# USB.net
KiCad netlist of a schematic drawn in EasyEDA Pro
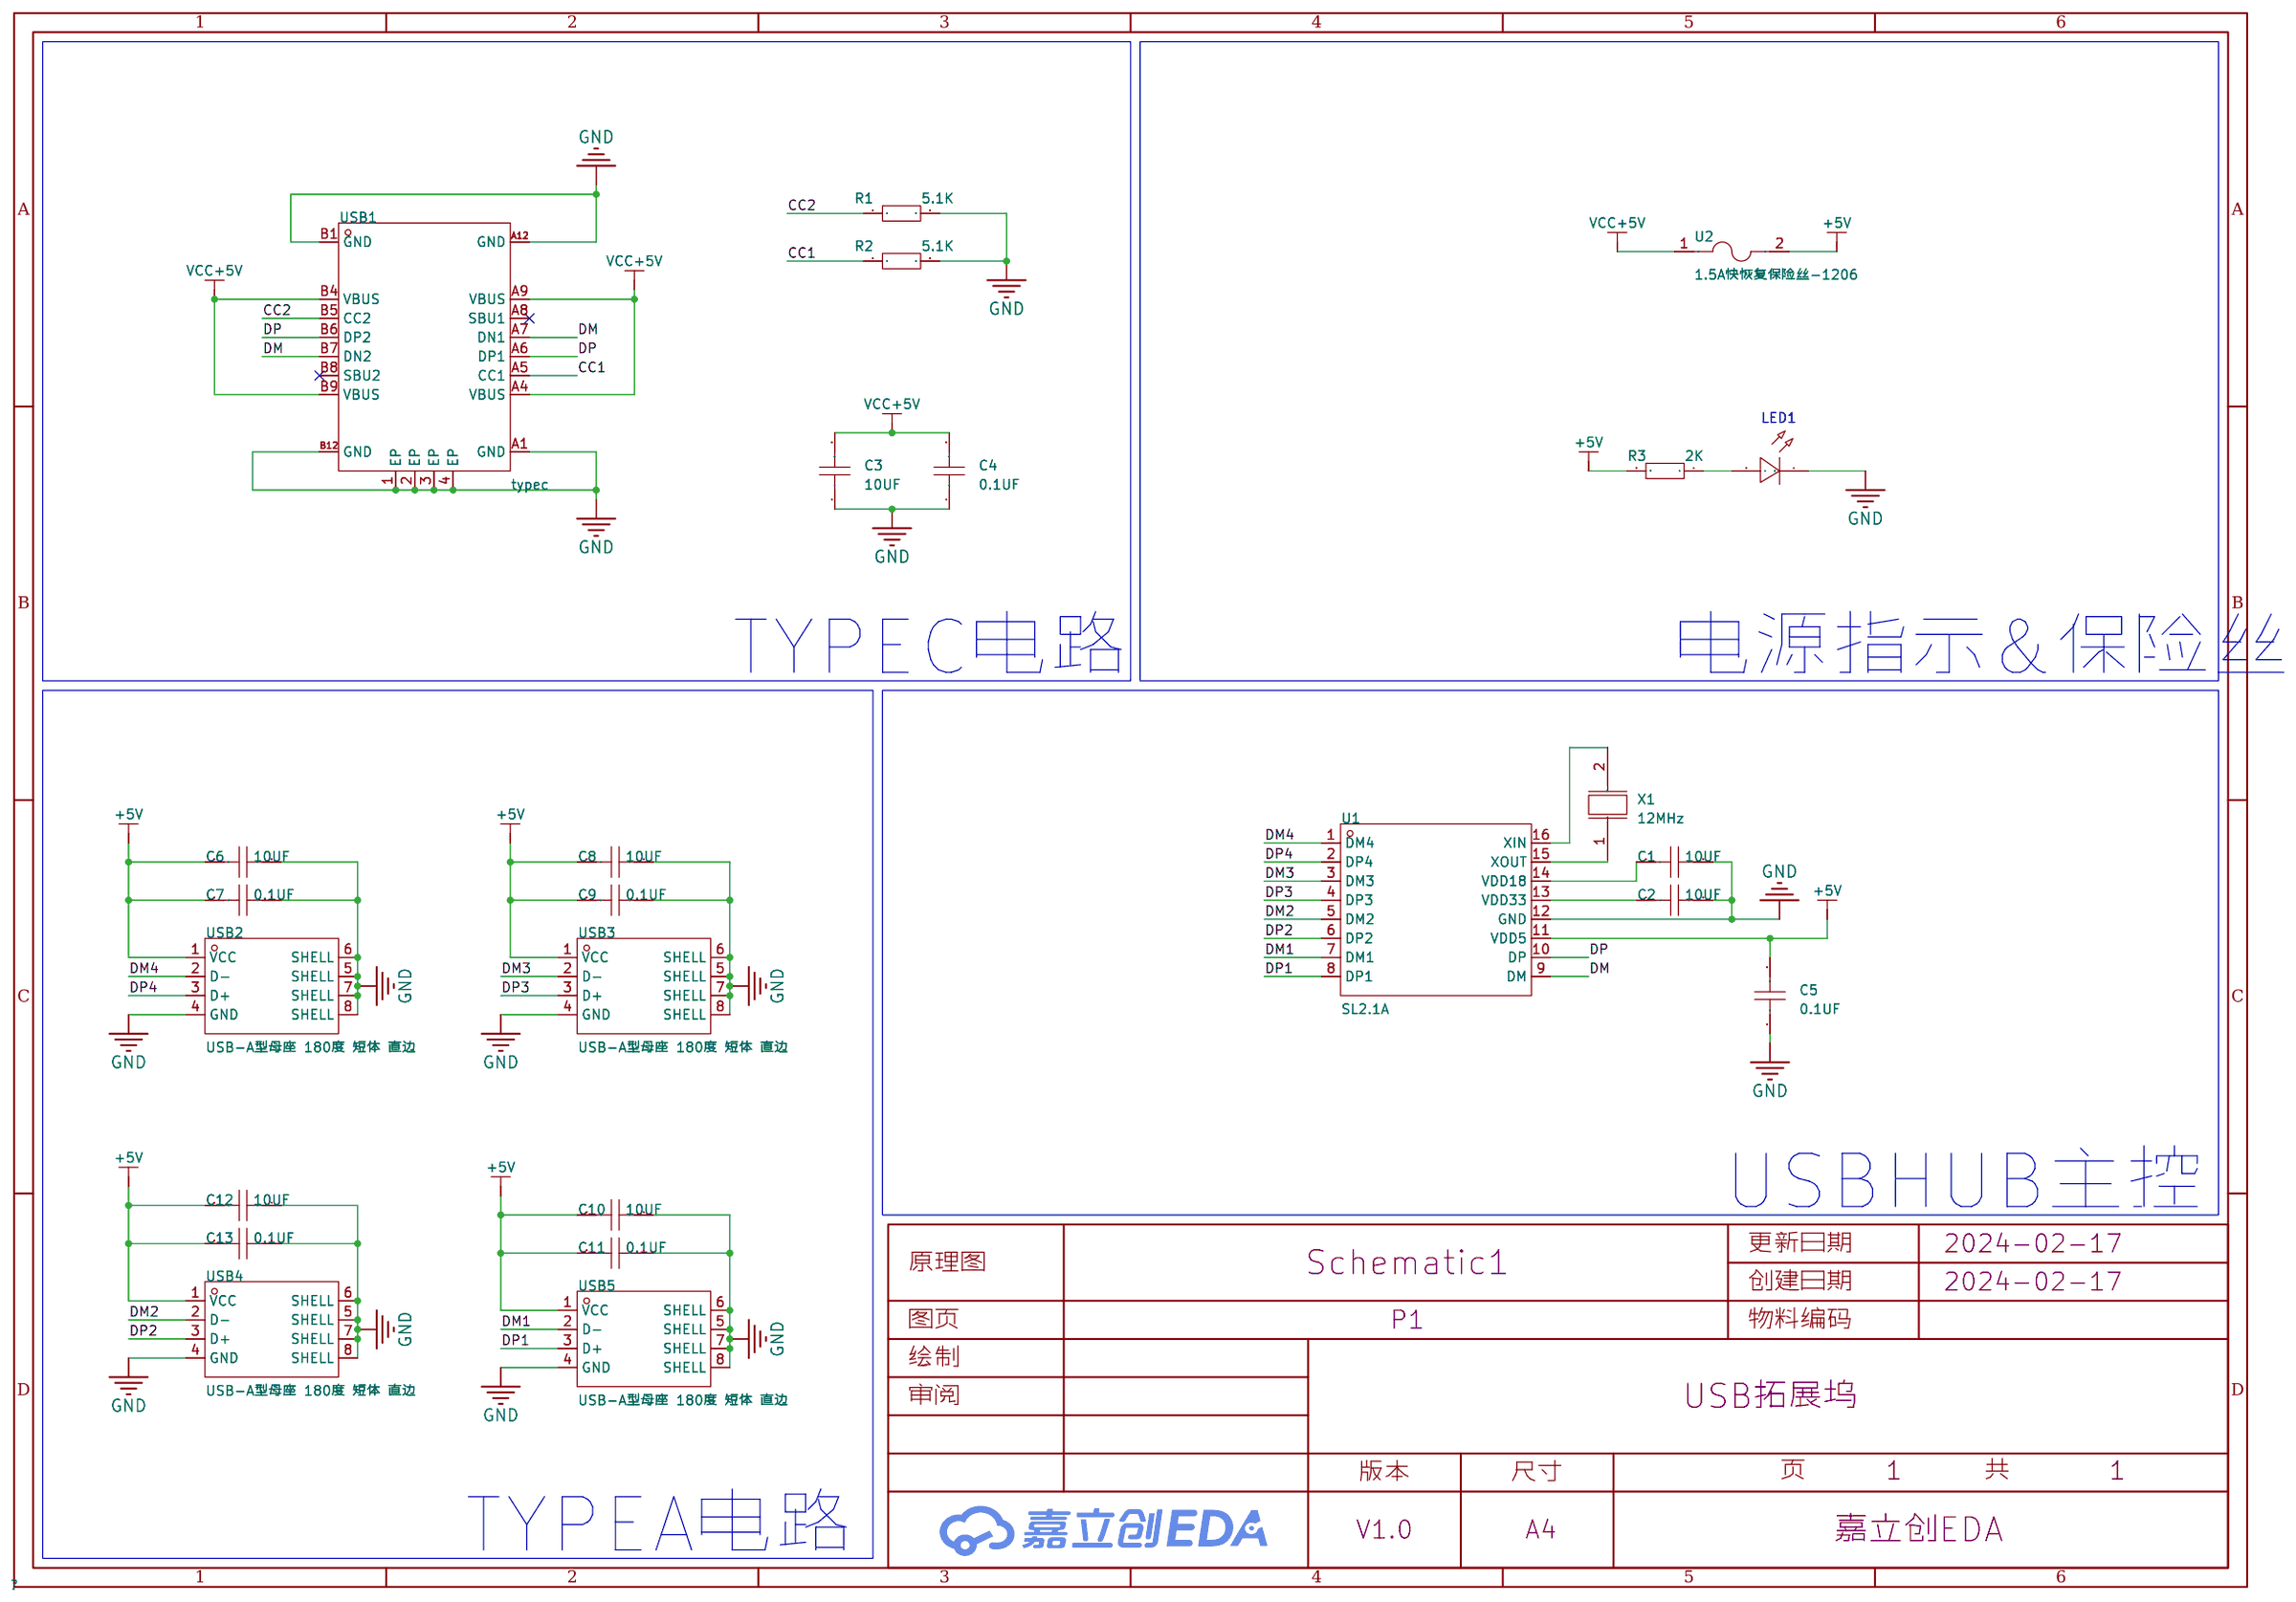
[diagram p0: schematic sheet]

(export (version "E")
  (design (tool "Eeschema 10.0.6"))
  (components
    (comp (ref "C1")
      (value "10UF")
      (footprint "easyedapro:C0805")
      (libsource (lib "easyedapro") (part "CapAcitance"))
    )
    (comp (ref "C2")
      (value "10UF")
      (footprint "easyedapro:C0805")
      (libsource (lib "easyedapro") (part "CapAcitance"))
    )
    (comp (ref "C3")
      (value "10UF")
      (footprint "easyedapro:C0805")
      (libsource (lib "easyedapro") (part "CapAcitance"))
    )
    (comp (ref "C4")
      (value "0.1UF")
      (footprint "easyedapro:C0805")
      (libsource (lib "easyedapro") (part "CapAcitance"))
    )
    (comp (ref "C5")
      (value "0.1UF")
      (footprint "easyedapro:C0805")
      (libsource (lib "easyedapro") (part "CapAcitance"))
    )
    (comp (ref "C6")
      (value "10UF")
      (footprint "easyedapro:C0805")
      (libsource (lib "easyedapro") (part "CapAcitance"))
    )
    (comp (ref "C7")
      (value "0.1UF")
      (footprint "easyedapro:C0805")
      (libsource (lib "easyedapro") (part "CapAcitance"))
    )
    (comp (ref "C8")
      (value "10UF")
      (footprint "easyedapro:C0805")
      (libsource (lib "easyedapro") (part "CapAcitance"))
    )
    (comp (ref "C9")
      (value "0.1UF")
      (footprint "easyedapro:C0805")
      (libsource (lib "easyedapro") (part "CapAcitance"))
    )
    (comp (ref "C10")
      (value "10UF")
      (footprint "easyedapro:C0805")
      (libsource (lib "easyedapro") (part "CapAcitance"))
    )
    (comp (ref "C11")
      (value "0.1UF")
      (footprint "easyedapro:C0805")
      (libsource (lib "easyedapro") (part "CapAcitance"))
    )
    (comp (ref "C12")
      (value "10UF")
      (footprint "easyedapro:C0805")
      (libsource (lib "easyedapro") (part "CapAcitance"))
    )
    (comp (ref "C13")
      (value "0.1UF")
      (footprint "easyedapro:C0805")
      (libsource (lib "easyedapro") (part "CapAcitance"))
    )
    (comp (ref "LED1")
      (value "~")
      (footprint "easyedapro:LED_0805")
      (libsource (lib "easyedapro") (part "LED_G"))
    )
    (comp (ref "R1") (value "5.1K") (footprint "easyedapro:R0805") (libsource (lib "easyedapro") (part "电阻")))
    (comp (ref "R2") (value "5.1K") (footprint "easyedapro:R0805") (libsource (lib "easyedapro") (part "电阻")))
    (comp (ref "R3") (value "2K") (footprint "easyedapro:R0805") (libsource (lib "easyedapro") (part "电阻")))
    (comp (ref "U1")
      (value "SL2.1A")
      (footprint "easyedapro:SOP-16_L10.0-W3.9-P1.27-LS6.0-BL")
      (description "应用功能:集线器;接口协议:-;")
      (fields (field (name "Manufacturer") "CoreChips(和芯润德)"))
      (libsource (lib "easyedapro") (part "SL2.1A"))
    )
    (comp (ref "U2")
      (value "1.5A快恢复保险丝-1206")
      (footprint "easyedapro:F1206")
      (libsource (lib "easyedapro") (part "1.5A快恢复保险丝-1206"))
    )
    (comp (ref "USB1")
      (value "typec")
      (footprint "easyedapro:USB-C-SMD_KH-TYPE-C-16P")
      (libsource (lib "easyedapro") (part "TYPEC_C9900016956"))
    )
    (comp (ref "USB2")
      (value "USB-A型母座 180度 短体 直边")
      (footprint "easyedapro:USB-A-SMD_WT_C9900004571")
      (libsource (lib "easyedapro") (part "USB-A型母座 180度 短体 直边"))
    )
    (comp (ref "USB3")
      (value "USB-A型母座 180度 短体 直边")
      (footprint "easyedapro:USB-A-SMD_WT_C9900004571")
      (libsource (lib "easyedapro") (part "USB-A型母座 180度 短体 直边"))
    )
    (comp (ref "USB4")
      (value "USB-A型母座 180度 短体 直边")
      (footprint "easyedapro:USB-A-SMD_WT_C9900004571")
      (libsource (lib "easyedapro") (part "USB-A型母座 180度 短体 直边"))
    )
    (comp (ref "USB5")
      (value "USB-A型母座 180度 短体 直边")
      (footprint "easyedapro:USB-A-SMD_WT_C9900004571")
      (libsource (lib "easyedapro") (part "USB-A型母座 180度 短体 直边"))
    )
    (comp (ref "X1")
      (value "12MHz")
      (footprint "easyedapro:CRYSTAL-SMD_L5.0-W3.2-1-A")
      (libsource (lib "easyedapro") (part "12MHZ"))
    )
  )
  (nets
    (net (code "1") (name "+5V") (class "Default")
      (node (ref "C10") (pin "2") (pinfunction "2_2") (pintype "input"))
      (node (ref "C11") (pin "2") (pinfunction "2_2") (pintype "input"))
      (node (ref "C12") (pin "2") (pinfunction "2_2") (pintype "input"))
      (node (ref "C13") (pin "2") (pinfunction "2_2") (pintype "input"))
      (node (ref "C5") (pin "2") (pinfunction "2_2") (pintype "input"))
      (node (ref "C6") (pin "2") (pinfunction "2_2") (pintype "input"))
      (node (ref "C7") (pin "2") (pinfunction "2_2") (pintype "input"))
      (node (ref "C8") (pin "2") (pinfunction "2_2") (pintype "input"))
      (node (ref "C9") (pin "2") (pinfunction "2_2") (pintype "input"))
      (node (ref "R3") (pin "2") (pinfunction "2_2") (pintype "input"))
      (node (ref "U1") (pin "11") (pinfunction "VDD5_11") (pintype "unspecified"))
      (node (ref "U2") (pin "2") (pinfunction "2_2") (pintype "input"))
      (node (ref "USB2") (pin "1") (pinfunction "VCC_1") (pintype "input"))
      (node (ref "USB3") (pin "1") (pinfunction "VCC_1") (pintype "input"))
      (node (ref "USB4") (pin "1") (pinfunction "VCC_1") (pintype "input"))
      (node (ref "USB5") (pin "1") (pinfunction "VCC_1") (pintype "input"))
    )
    (net (code "2") (name "/CC1") (class "Default")
      (node (ref "R2") (pin "1") (pinfunction "1_1") (pintype "input"))
      (node (ref "USB1") (pin "A5") (pinfunction "CC1_A5") (pintype "input"))
    )
    (net (code "3") (name "/CC2") (class "Default")
      (node (ref "R1") (pin "1") (pinfunction "1_1") (pintype "input"))
      (node (ref "USB1") (pin "B5") (pinfunction "CC2_B5") (pintype "input"))
    )
    (net (code "4") (name "/DM") (class "Default")
      (node (ref "U1") (pin "9") (pinfunction "DM_9") (pintype "unspecified"))
      (node (ref "USB1") (pin "A7") (pinfunction "DN1_A7") (pintype "input"))
      (node (ref "USB1") (pin "B7") (pinfunction "DN2_B7") (pintype "input"))
    )
    (net (code "5") (name "/DM1") (class "Default")
      (node (ref "U1") (pin "7") (pinfunction "DM1_7") (pintype "unspecified"))
      (node (ref "USB5") (pin "2") (pinfunction "D-_2") (pintype "input"))
    )
    (net (code "6") (name "/DM2") (class "Default")
      (node (ref "U1") (pin "5") (pinfunction "DM2_5") (pintype "unspecified"))
      (node (ref "USB4") (pin "2") (pinfunction "D-_2") (pintype "input"))
    )
    (net (code "7") (name "/DM3") (class "Default")
      (node (ref "U1") (pin "3") (pinfunction "DM3_3") (pintype "unspecified"))
      (node (ref "USB3") (pin "2") (pinfunction "D-_2") (pintype "input"))
    )
    (net (code "8") (name "/DM4") (class "Default")
      (node (ref "U1") (pin "1") (pinfunction "DM4_1") (pintype "unspecified"))
      (node (ref "USB2") (pin "2") (pinfunction "D-_2") (pintype "input"))
    )
    (net (code "9") (name "/DP") (class "Default")
      (node (ref "U1") (pin "10") (pinfunction "DP_10") (pintype "unspecified"))
      (node (ref "USB1") (pin "A6") (pinfunction "DP1_A6") (pintype "input"))
      (node (ref "USB1") (pin "B6") (pinfunction "DP2_B6") (pintype "input"))
    )
    (net (code "10") (name "/DP1") (class "Default")
      (node (ref "U1") (pin "8") (pinfunction "DP1_8") (pintype "unspecified"))
      (node (ref "USB5") (pin "3") (pinfunction "D+_3") (pintype "input"))
    )
    (net (code "11") (name "/DP2") (class "Default")
      (node (ref "U1") (pin "6") (pinfunction "DP2_6") (pintype "unspecified"))
      (node (ref "USB4") (pin "3") (pinfunction "D+_3") (pintype "input"))
    )
    (net (code "12") (name "/DP3") (class "Default")
      (node (ref "U1") (pin "4") (pinfunction "DP3_4") (pintype "unspecified"))
      (node (ref "USB3") (pin "3") (pinfunction "D+_3") (pintype "input"))
    )
    (net (code "13") (name "/DP4") (class "Default")
      (node (ref "U1") (pin "2") (pinfunction "DP4_2") (pintype "unspecified"))
      (node (ref "USB2") (pin "3") (pinfunction "D+_3") (pintype "input"))
    )
    (net (code "14") (name "GND") (class "Default")
      (node (ref "C1") (pin "2") (pinfunction "2_2") (pintype "input"))
      (node (ref "C10") (pin "1") (pinfunction "1_1") (pintype "input"))
      (node (ref "C11") (pin "1") (pinfunction "1_1") (pintype "input"))
      (node (ref "C12") (pin "1") (pinfunction "1_1") (pintype "input"))
      (node (ref "C13") (pin "1") (pinfunction "1_1") (pintype "input"))
      (node (ref "C2") (pin "2") (pinfunction "2_2") (pintype "input"))
      (node (ref "C3") (pin "1") (pinfunction "1_1") (pintype "input"))
      (node (ref "C4") (pin "1") (pinfunction "1_1") (pintype "input"))
      (node (ref "C5") (pin "1") (pinfunction "1_1") (pintype "input"))
      (node (ref "C6") (pin "1") (pinfunction "1_1") (pintype "input"))
      (node (ref "C7") (pin "1") (pinfunction "1_1") (pintype "input"))
      (node (ref "C8") (pin "1") (pinfunction "1_1") (pintype "input"))
      (node (ref "C9") (pin "1") (pinfunction "1_1") (pintype "input"))
      (node (ref "LED1") (pin "1") (pinfunction "C_1") (pintype "input"))
      (node (ref "R1") (pin "2") (pinfunction "2_2") (pintype "input"))
      (node (ref "R2") (pin "2") (pinfunction "2_2") (pintype "input"))
      (node (ref "U1") (pin "12") (pinfunction "GND_12") (pintype "unspecified"))
      (node (ref "USB1") (pin "1") (pinfunction "EP_1") (pintype "input"))
      (node (ref "USB1") (pin "2") (pinfunction "EP_2") (pintype "input"))
      (node (ref "USB1") (pin "3") (pinfunction "EP_3") (pintype "input"))
      (node (ref "USB1") (pin "4") (pinfunction "EP_4") (pintype "input"))
      (node (ref "USB1") (pin "A1") (pinfunction "GND_A1") (pintype "input"))
      (node (ref "USB1") (pin "A12") (pinfunction "GND_A12") (pintype "input"))
      (node (ref "USB1") (pin "B1") (pinfunction "GND_B1") (pintype "input"))
      (node (ref "USB1") (pin "B12") (pinfunction "GND_B12") (pintype "input"))
      (node (ref "USB2") (pin "4") (pinfunction "GND_4") (pintype "input"))
      (node (ref "USB2") (pin "5") (pinfunction "SHELL_5") (pintype "input"))
      (node (ref "USB2") (pin "6") (pinfunction "SHELL_6") (pintype "input"))
      (node (ref "USB2") (pin "7") (pinfunction "SHELL_7") (pintype "input"))
      (node (ref "USB2") (pin "8") (pinfunction "SHELL_8") (pintype "input"))
      (node (ref "USB3") (pin "4") (pinfunction "GND_4") (pintype "input"))
      (node (ref "USB3") (pin "5") (pinfunction "SHELL_5") (pintype "input"))
      (node (ref "USB3") (pin "6") (pinfunction "SHELL_6") (pintype "input"))
      (node (ref "USB3") (pin "7") (pinfunction "SHELL_7") (pintype "input"))
      (node (ref "USB3") (pin "8") (pinfunction "SHELL_8") (pintype "input"))
      (node (ref "USB4") (pin "4") (pinfunction "GND_4") (pintype "input"))
      (node (ref "USB4") (pin "5") (pinfunction "SHELL_5") (pintype "input"))
      (node (ref "USB4") (pin "6") (pinfunction "SHELL_6") (pintype "input"))
      (node (ref "USB4") (pin "7") (pinfunction "SHELL_7") (pintype "input"))
      (node (ref "USB4") (pin "8") (pinfunction "SHELL_8") (pintype "input"))
      (node (ref "USB5") (pin "4") (pinfunction "GND_4") (pintype "input"))
      (node (ref "USB5") (pin "5") (pinfunction "SHELL_5") (pintype "input"))
      (node (ref "USB5") (pin "6") (pinfunction "SHELL_6") (pintype "input"))
      (node (ref "USB5") (pin "7") (pinfunction "SHELL_7") (pintype "input"))
      (node (ref "USB5") (pin "8") (pinfunction "SHELL_8") (pintype "input"))
    )
    (net (code "15") (name "Net-(LED1-A)") (class "Default")
      (node (ref "LED1") (pin "2") (pinfunction "A_2") (pintype "input"))
      (node (ref "R3") (pin "1") (pinfunction "1_1") (pintype "input"))
    )
    (net (code "16") (name "Net-(U1-VDD18)") (class "Default")
      (node (ref "C1") (pin "1") (pinfunction "1_1") (pintype "input"))
      (node (ref "U1") (pin "14") (pinfunction "VDD18_14") (pintype "unspecified"))
    )
    (net (code "17") (name "Net-(U1-VDD33)") (class "Default")
      (node (ref "C2") (pin "1") (pinfunction "1_1") (pintype "input"))
      (node (ref "U1") (pin "13") (pinfunction "VDD33_13") (pintype "unspecified"))
    )
    (net (code "18") (name "Net-(U1-XIN)") (class "Default")
      (node (ref "U1") (pin "16") (pinfunction "XIN_16") (pintype "unspecified"))
      (node (ref "X1") (pin "2") (pinfunction "2_2") (pintype "input"))
    )
    (net (code "19") (name "Net-(U1-XOUT)") (class "Default")
      (node (ref "U1") (pin "15") (pinfunction "XOUT_15") (pintype "unspecified"))
      (node (ref "X1") (pin "1") (pinfunction "1_1") (pintype "input"))
    )
    (net (code "20") (name "VCC+5V") (class "Default")
      (node (ref "C3") (pin "2") (pinfunction "2_2") (pintype "input"))
      (node (ref "C4") (pin "2") (pinfunction "2_2") (pintype "input"))
      (node (ref "U2") (pin "1") (pinfunction "1_1") (pintype "input"))
      (node (ref "USB1") (pin "A4") (pinfunction "VBUS_A4") (pintype "input"))
      (node (ref "USB1") (pin "A9") (pinfunction "VBUS_A9") (pintype "input"))
      (node (ref "USB1") (pin "B4") (pinfunction "VBUS_B4") (pintype "input"))
      (node (ref "USB1") (pin "B9") (pinfunction "VBUS_B9") (pintype "input"))
    )
    (net (code "21") (name "unconnected-(USB1-SBU1-PadA8)") (class "Default")
      (node (ref "USB1") (pin "A8") (pinfunction "SBU1_A8") (pintype "input+no_connect"))
    )
    (net (code "22") (name "unconnected-(USB1-SBU2-PadB8)") (class "Default")
      (node (ref "USB1") (pin "B8") (pinfunction "SBU2_B8") (pintype "input+no_connect"))
    )
  )
)
